# dht11.net
KiCad netlist of a schematic drawn in EAGLE
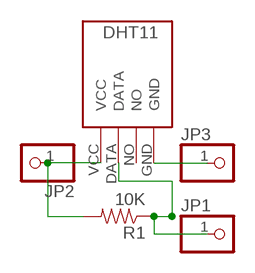
[diagram p0: schematic, sheet 1]

(export (version "E")
  (design (tool "Eeschema 10.0.6"))
  (components
    (comp (ref "JP1")
      (value "PINHD-1X1")
      (footprint "eagle-import:1X01")
      (libsource (lib "eagle-import") (part "PINHD-1X1"))
    )
    (comp (ref "JP2")
      (value "PINHD-1X1")
      (footprint "eagle-import:1X01")
      (libsource (lib "eagle-import") (part "PINHD-1X1"))
    )
    (comp (ref "JP3")
      (value "PINHD-1X1")
      (footprint "eagle-import:1X01")
      (libsource (lib "eagle-import") (part "PINHD-1X1"))
    )
    (comp (ref "R1")
      (value "10K")
      (footprint "eagle-import:AXIAL-0.3")
      (libsource (lib "eagle-import") (part "1KOHM-1/4W-1%(PTH)"))
    )
    (comp (ref "U$1")
      (value "DHT11")
      (footprint "eagle-import:DHT11")
      (libsource (lib "eagle-import") (part "DHT11"))
    )
  )
  (nets
    (net (code "1") (name "Net-(JP3-Pad1)") (class "Default")
      (node (ref "JP3") (pin "1") (pinfunction "1_1") (pintype "passive"))
      (node (ref "U$1") (pin "GND") (pinfunction "GND_GND") (pintype "bidirectional"))
    )
    (net (code "2") (name "Net-(R1-1)") (class "Default")
      (node (ref "JP1") (pin "1") (pinfunction "1_1") (pintype "passive"))
      (node (ref "R1") (pin "P$1") (pinfunction "1_P$1") (pintype "passive"))
      (node (ref "U$1") (pin "DATA") (pinfunction "DATA_DATA") (pintype "bidirectional"))
    )
    (net (code "3") (name "Net-(R1-2)") (class "Default")
      (node (ref "JP2") (pin "1") (pinfunction "1_1") (pintype "passive"))
      (node (ref "R1") (pin "P$2") (pinfunction "2_P$2") (pintype "passive"))
      (node (ref "U$1") (pin "VCC") (pinfunction "VCC_VCC") (pintype "bidirectional"))
    )
    (net (code "4") (name "unconnected-(U$1-PadNO)") (class "Default")
      (node (ref "U$1") (pin "NO") (pinfunction "NO_NO") (pintype "bidirectional"))
    )
  )
)
